# MCU.net
KiCad netlist of a schematic drawn in Altium Designer
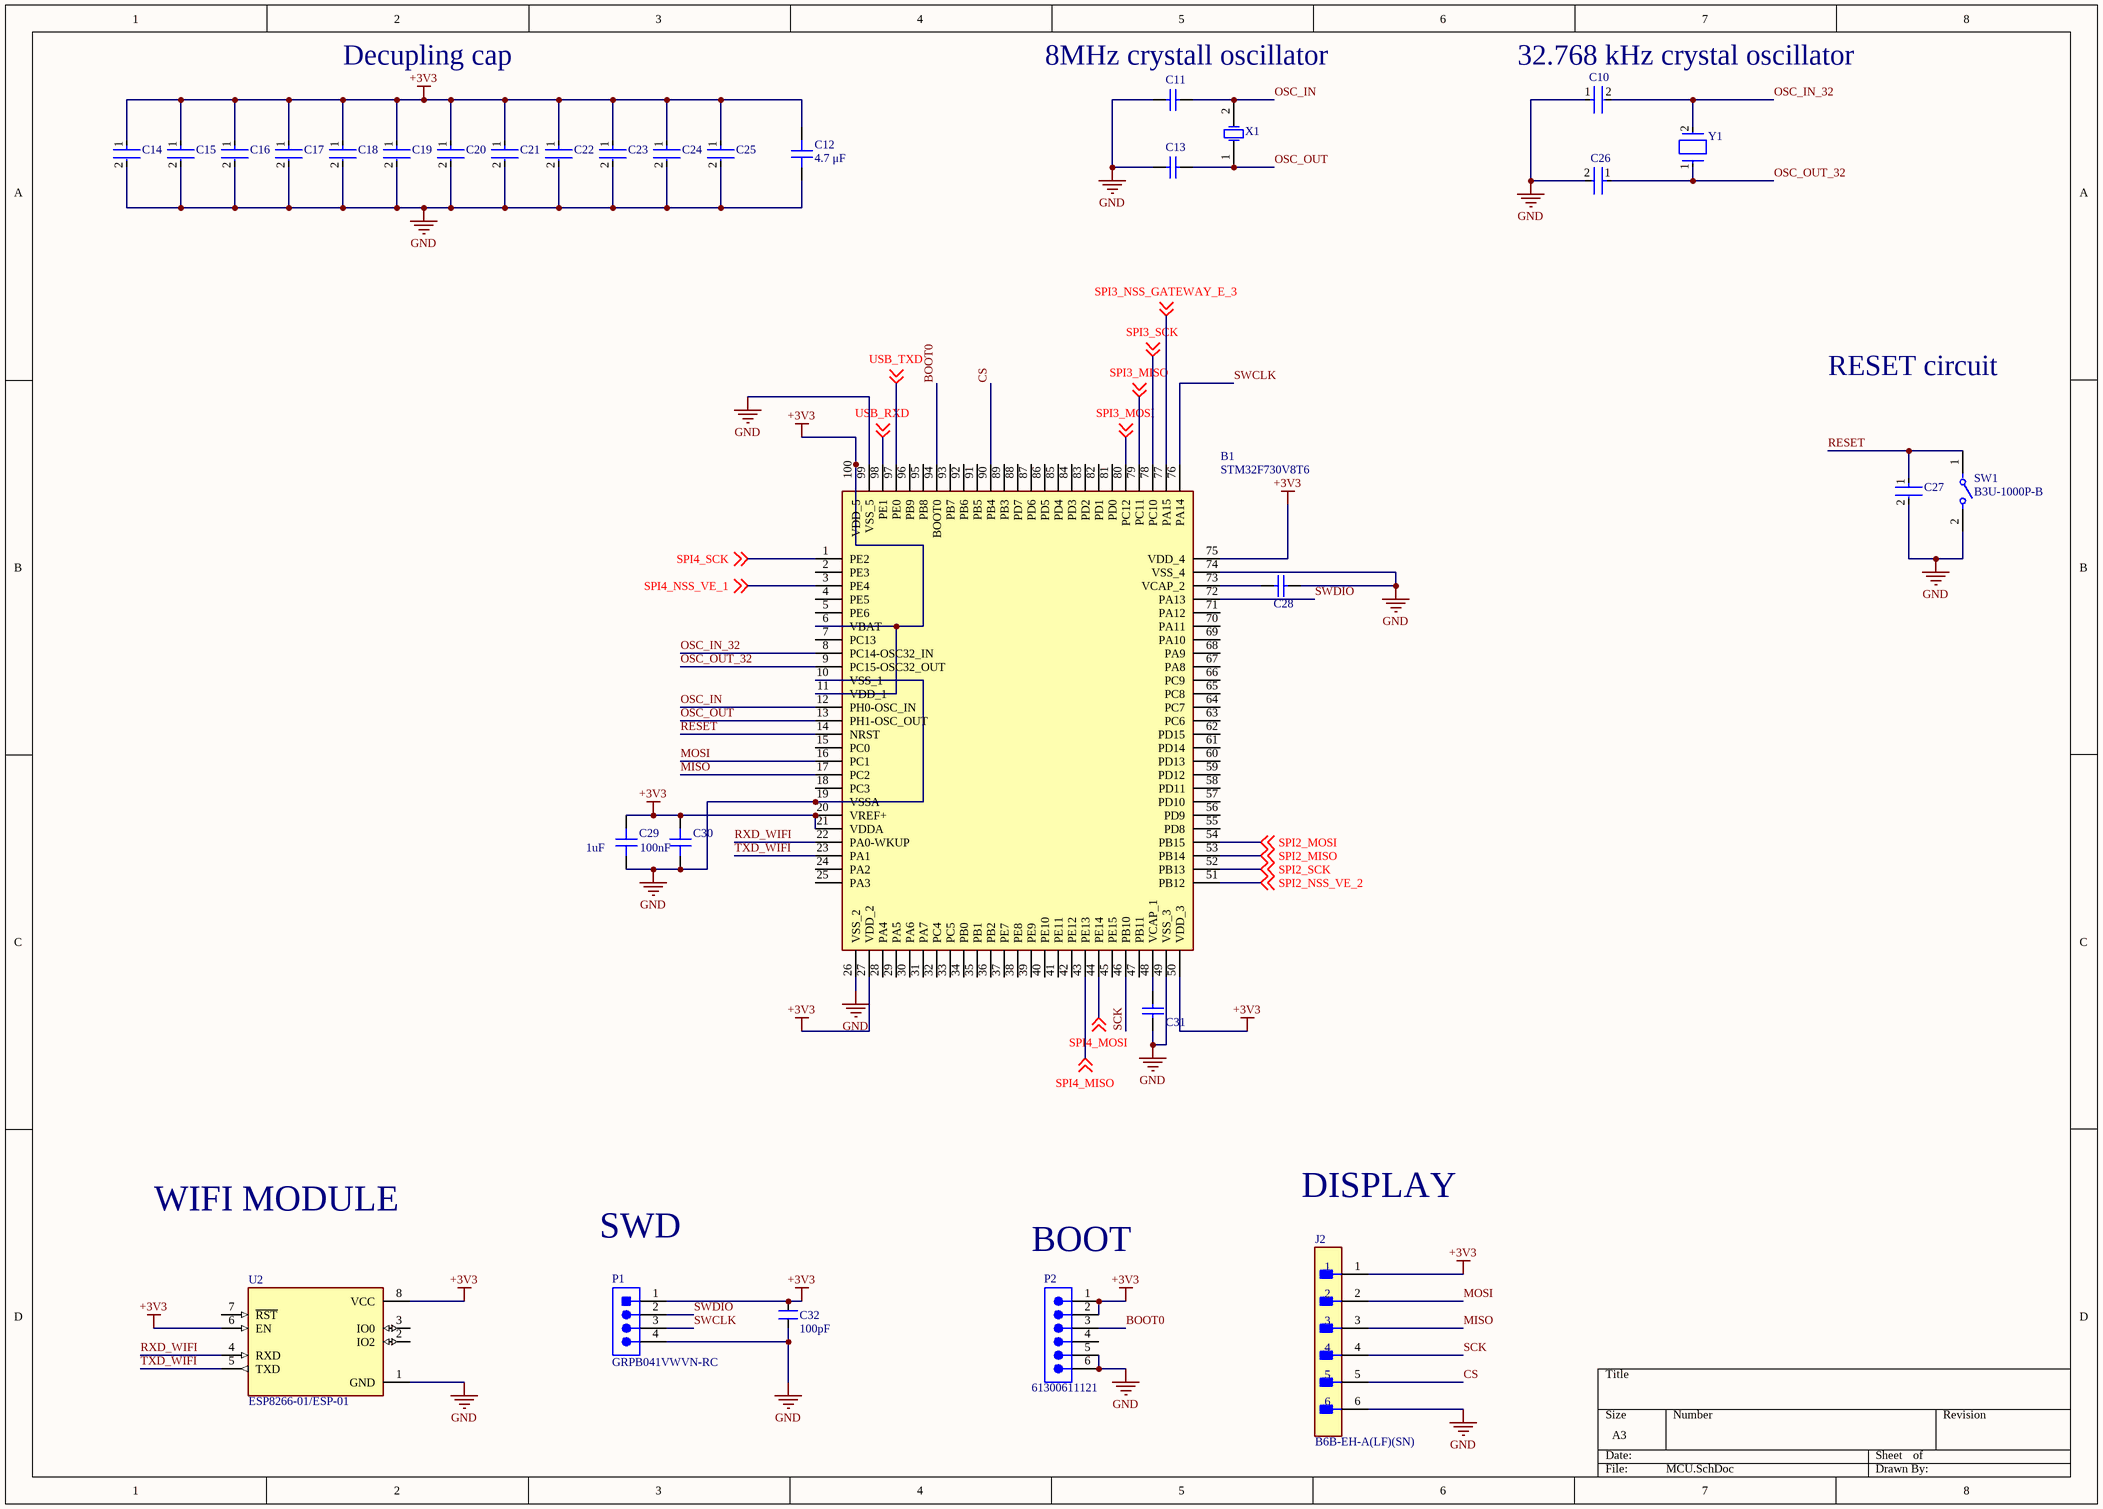
[diagram p0: MCU.SchDoc]

(export (version "E")
  (design (tool "Eeschema 10.0.6"))
  (components
    (comp (ref "B1")
      (value "STM32F730V8T6")
      (footprint "QFP50P1600X1600X160-100N")
      (description "STMICROELECTRONICS - STM32F730V8T6 - MCU, 32BIT, 216MHZ, LQFP-100")
      (fields (field (name "MOUSER PART NUMBER") "511-STM32F730V8T6"))
      (libsource (lib "STM32F730V8T6") (part "STM32F730V8T6"))
    )
    (comp (ref "C10")
      (value "C1005C0G1H070D050BA")
      (footprint "FP-C1005-050-0_05-IPC_A")
      (description "Multilayer Ceramic Capacitors 7pF ±0.5pF 50V C0G SMD 0402")
      (libsource (lib "Altium Content Vault") (part "b4654b650e69147ec39a6b967a45e02"))
    )
    (comp (ref "C11")
      (value "CC0603JRNPO9BN180")
      (footprint "CAPC1608X90X40LL10T20")
      (description "Chip Capacitor, 18 pF, +/- 5%, 50 V, -55 to 125 degC, 0603 (1608 Metric), RoHS, Tape and Reel")
      (fields (field (name "TOLERANCE") "1%"))
      (libsource (lib "Altium Content Vault") (part "CAP-NP-2"))
    )
    (comp (ref "C12")
      (value "4.7 μF")
      (footprint "CAP 0402_1005")
      (description "SMT Capacitor")
      (libsource (lib "Capacitor") (part "Cap 0402"))
    )
    (comp (ref "C13")
      (value "CC0603JRNPO9BN180")
      (footprint "CAPC1608X90X40LL10T20")
      (description "Chip Capacitor, 18 pF, +/- 5%, 50 V, -55 to 125 degC, 0603 (1608 Metric), RoHS, Tape and Reel")
      (fields (field (name "TOLERANCE") "1%"))
      (libsource (lib "Altium Content Vault") (part "CAP-NP-2"))
    )
    (comp (ref "C14")
      (value "GRM155R71H104KE14D")
      (footprint "FP-GRM155-0_05-IPC_B")
      (description "Chip Multilayer Ceramic Capacitors for General Purpose, 0402, 0.10uF, X7R, 15%, 10%, 50V")
      (fields (field (name "VOLTAGE") "50V") (field (name "TOLERANCE") "10%"))
      (libsource (lib "Altium Content Vault") (part "02cd4be3c70576c341d710602a673aa"))
    )
    (comp (ref "C15")
      (value "GRM155R71H104KE14D")
      (footprint "FP-GRM155-0_05-IPC_B")
      (description "Chip Multilayer Ceramic Capacitors for General Purpose, 0402, 0.10uF, X7R, 15%, 10%, 50V")
      (fields (field (name "VOLTAGE") "50V") (field (name "TOLERANCE") "10%"))
      (libsource (lib "Altium Content Vault") (part "02cd4be3c70576c341d710602a673aa"))
    )
    (comp (ref "C16")
      (value "GRM155R71H104KE14D")
      (footprint "FP-GRM155-0_05-IPC_B")
      (description "Chip Multilayer Ceramic Capacitors for General Purpose, 0402, 0.10uF, X7R, 15%, 10%, 50V")
      (fields (field (name "VOLTAGE") "50V") (field (name "TOLERANCE") "10%"))
      (libsource (lib "Altium Content Vault") (part "02cd4be3c70576c341d710602a673aa"))
    )
    (comp (ref "C17")
      (value "GRM155R71H104KE14D")
      (footprint "FP-GRM155-0_05-IPC_B")
      (description "Chip Multilayer Ceramic Capacitors for General Purpose, 0402, 0.10uF, X7R, 15%, 10%, 50V")
      (fields (field (name "VOLTAGE") "50V") (field (name "TOLERANCE") "10%"))
      (libsource (lib "Altium Content Vault") (part "02cd4be3c70576c341d710602a673aa"))
    )
    (comp (ref "C18")
      (value "GRM155R71H104KE14D")
      (footprint "FP-GRM155-0_05-IPC_B")
      (description "Chip Multilayer Ceramic Capacitors for General Purpose, 0402, 0.10uF, X7R, 15%, 10%, 50V")
      (fields (field (name "VOLTAGE") "50V") (field (name "TOLERANCE") "10%"))
      (libsource (lib "Altium Content Vault") (part "02cd4be3c70576c341d710602a673aa"))
    )
    (comp (ref "C19")
      (value "GRM155R71H104KE14D")
      (footprint "FP-GRM155-0_05-IPC_B")
      (description "Chip Multilayer Ceramic Capacitors for General Purpose, 0402, 0.10uF, X7R, 15%, 10%, 50V")
      (fields (field (name "VOLTAGE") "50V") (field (name "TOLERANCE") "10%"))
      (libsource (lib "Altium Content Vault") (part "02cd4be3c70576c341d710602a673aa"))
    )
    (comp (ref "C20")
      (value "GRM155R71H104KE14D")
      (footprint "FP-GRM155-0_05-IPC_B")
      (description "Chip Multilayer Ceramic Capacitors for General Purpose, 0402, 0.10uF, X7R, 15%, 10%, 50V")
      (fields (field (name "VOLTAGE") "50V") (field (name "TOLERANCE") "10%"))
      (libsource (lib "Altium Content Vault") (part "02cd4be3c70576c341d710602a673aa"))
    )
    (comp (ref "C21")
      (value "GRM155R71H104KE14D")
      (footprint "FP-GRM155-0_05-IPC_B")
      (description "Chip Multilayer Ceramic Capacitors for General Purpose, 0402, 0.10uF, X7R, 15%, 10%, 50V")
      (fields (field (name "VOLTAGE") "50V") (field (name "TOLERANCE") "10%"))
      (libsource (lib "Altium Content Vault") (part "02cd4be3c70576c341d710602a673aa"))
    )
    (comp (ref "C22")
      (value "GRM155R71H104KE14D")
      (footprint "FP-GRM155-0_05-IPC_B")
      (description "Chip Multilayer Ceramic Capacitors for General Purpose, 0402, 0.10uF, X7R, 15%, 10%, 50V")
      (fields (field (name "VOLTAGE") "50V") (field (name "TOLERANCE") "10%"))
      (libsource (lib "Altium Content Vault") (part "02cd4be3c70576c341d710602a673aa"))
    )
    (comp (ref "C23")
      (value "GRM155R71H104KE14D")
      (footprint "FP-GRM155-0_05-IPC_B")
      (description "Chip Multilayer Ceramic Capacitors for General Purpose, 0402, 0.10uF, X7R, 15%, 10%, 50V")
      (fields (field (name "VOLTAGE") "50V") (field (name "TOLERANCE") "10%"))
      (libsource (lib "Altium Content Vault") (part "02cd4be3c70576c341d710602a673aa"))
    )
    (comp (ref "C24")
      (value "GRM155R71H104KE14D")
      (footprint "FP-GRM155-0_05-IPC_B")
      (description "Chip Multilayer Ceramic Capacitors for General Purpose, 0402, 0.10uF, X7R, 15%, 10%, 50V")
      (fields (field (name "VOLTAGE") "50V") (field (name "TOLERANCE") "10%"))
      (libsource (lib "Altium Content Vault") (part "02cd4be3c70576c341d710602a673aa"))
    )
    (comp (ref "C25")
      (value "GRM155R71H104KE14D")
      (footprint "FP-GRM155-0_05-IPC_B")
      (description "Chip Multilayer Ceramic Capacitors for General Purpose, 0402, 0.10uF, X7R, 15%, 10%, 50V")
      (fields (field (name "VOLTAGE") "50V") (field (name "TOLERANCE") "10%"))
      (libsource (lib "Altium Content Vault") (part "02cd4be3c70576c341d710602a673aa"))
    )
    (comp (ref "C26")
      (value "C1005C0G1H070D050BA")
      (footprint "FP-C1005-050-0_05-IPC_A")
      (description "Multilayer Ceramic Capacitors 7pF ±0.5pF 50V C0G SMD 0402")
      (libsource (lib "Altium Content Vault") (part "b4654b650e69147ec39a6b967a45e02"))
    )
    (comp (ref "C27")
      (value "GRM155R71H104KE14D")
      (footprint "FP-GRM155-0_05-IPC_B")
      (description "Chip Multilayer Ceramic Capacitors for General Purpose, 0402, 0.10uF, X7R, 15%, 10%, 50V")
      (fields (field (name "VOLTAGE") "50V") (field (name "TOLERANCE") "10%"))
      (libsource (lib "Altium Content Vault") (part "02cd4be3c70576c341d710602a673aa"))
    )
    (comp (ref "C28")
      (value "C0603C225K9PACTU")
      (footprint "CAPC1608X90X35LL15T15")
      (fields (field (name "MANUFACTURER") "Kemet"))
      (libsource (lib "Altium Content Vault") (part "CAP"))
    )
    (comp (ref "C29")
      (value "1uF")
      (footprint "CAP 0402_1005")
      (description "SMT Capacitor")
      (libsource (lib "Capacitor") (part "Cap 0402"))
    )
    (comp (ref "C30")
      (value "100nF")
      (footprint "CAP 0402_1005")
      (description "SMT Capacitor")
      (libsource (lib "Capacitor") (part "Cap 0402"))
    )
    (comp (ref "C31")
      (value "C0603C225K9PACTU")
      (footprint "CAPC1608X90X35LL15T15")
      (fields (field (name "MANUFACTURER") "Kemet"))
      (libsource (lib "Altium Content Vault") (part "CAP"))
    )
    (comp (ref "C32")
      (value "100pF")
      (footprint "CAP_0805")
      (description "100pF ±5% 100V Ceramic Capacitor C0G, NP0 0805 (2012 Metric)")
      (fields
        (field (name "MANUFACTURER") "Murata")
        (field (name "MANUFACTURER PART NUMBER") "CL21C101JC61PNC")
      )
      (libsource (lib "ESTEEMPCBLIB") (part "CAP_100pF-100V-5%-0805"))
    )
    (comp (ref "J2")
      (value "B6B-EH-A(LF)(SN)")
      (footprint "FP-B6B-EH-A_LF_SN-MFG")
      (description "CONN HEADER VERT 6POS 2.5MM")
      (libsource (lib "Altium Content Vault") (part "f2cb566baf1c37ab5a3b8e90bbeafd6"))
    )
    (comp (ref "P1")
      (value "GRPB041VWVN-RC")
      (footprint "SLIN-GRPB041VWVN-RC_V")
      (fields (field (name "MANUFACTURER") "Sullins"))
      (libsource (lib "Altium Content Vault") (part "CN-1P-M-R4"))
    )
    (comp (ref "P2")
      (value "61300611121")
      (footprint "61300611121")
      (libsource (lib "Altium Content Vault") (part "Header_Male_1R_06P"))
    )
    (comp (ref "SW1")
      (value "B3U-1000P-B")
      (footprint "FP-B3U-1000P-B-MFG")
      (description "SWITCH TACTILE SPST-NO 0.05A 12V")
      (fields
        (field (name "OCTOPART") "https://octopart.com/b3u-1000p-b-omron-1057356")
        (field (name "MANUFACTURER") "Omron")
      )
      (libsource (lib "Altium Content Vault") (part "bb27bde45df87f1f469753f287ef5ae"))
    )
    (comp (ref "U2")
      (value "ESP8266-01/ESP-01")
      (footprint "XCVR_ESP8266-01/ESP-01")
      (libsource (lib "ESP8266 wifi module") (part "ESP8266-01/ESP-01"))
    )
    (comp (ref "X1")
      (value "ECS-80-18-5PX-TR")
      (footprint "ECS-80-18-5PX-TR_V")
      (description "Low Profile Quartz Crystal, 8.0 MHz, 2-Pin SMD, RoHS, Tape and Reel")
      (fields (field (name "TOLERANCE") "30PPM") (field (name "MANUFACTURER") "ECS"))
      (libsource (lib "Altium Content Vault") (part "XTAL_1-2-2"))
    )
    (comp (ref "Y1")
      (value "ABS07-32.768KHZ-7-T")
      (footprint "FP-ABS07-MFG")
      (description "Crystal 32.768kHz ±20ppm (Tol) 7pF FUND 70kΩ 2-Pin CSMD T/R")
      (fields (field (name "TOLERANCE") "20ppm"))
      (libsource (lib "Altium Content Vault") (part "c23a69dc6c9e2f18f2079038eb95dd1"))
    )
  )
  (nets
    (net (code "1") (name "+3V3") (class "Default")
      (node (ref "B1") (pin "100") (pinfunction "VDD_5_100") (pintype "passive"))
      (node (ref "B1") (pin "11") (pinfunction "VDD_1_11") (pintype "passive"))
      (node (ref "B1") (pin "20") (pinfunction "VREF+_20") (pintype "passive"))
      (node (ref "B1") (pin "21") (pinfunction "VDDA_21") (pintype "passive"))
      (node (ref "B1") (pin "27") (pinfunction "VDD_2_27") (pintype "passive"))
      (node (ref "B1") (pin "50") (pinfunction "VDD_3_50") (pintype "passive"))
      (node (ref "B1") (pin "6") (pinfunction "VBAT_6") (pintype "passive"))
      (node (ref "B1") (pin "75") (pinfunction "VDD_4_75") (pintype "passive"))
      (node (ref "C12") (pin "2") (pinfunction "2_2") (pintype "passive"))
      (node (ref "C14") (pin "1") (pinfunction "1_1") (pintype "passive"))
      (node (ref "C15") (pin "1") (pinfunction "1_1") (pintype "passive"))
      (node (ref "C16") (pin "1") (pinfunction "1_1") (pintype "passive"))
      (node (ref "C17") (pin "1") (pinfunction "1_1") (pintype "passive"))
      (node (ref "C18") (pin "1") (pinfunction "1_1") (pintype "passive"))
      (node (ref "C19") (pin "1") (pinfunction "1_1") (pintype "passive"))
      (node (ref "C20") (pin "1") (pinfunction "1_1") (pintype "passive"))
      (node (ref "C21") (pin "1") (pinfunction "1_1") (pintype "passive"))
      (node (ref "C22") (pin "1") (pinfunction "1_1") (pintype "passive"))
      (node (ref "C23") (pin "1") (pinfunction "1_1") (pintype "passive"))
      (node (ref "C24") (pin "1") (pinfunction "1_1") (pintype "passive"))
      (node (ref "C25") (pin "1") (pinfunction "1_1") (pintype "passive"))
      (node (ref "C29") (pin "2") (pinfunction "2_2") (pintype "passive"))
      (node (ref "C30") (pin "2") (pinfunction "2_2") (pintype "passive"))
      (node (ref "C32") (pin "2") (pinfunction "2_2") (pintype "passive"))
      (node (ref "J2") (pin "1") (pinfunction "1_1") (pintype "passive"))
      (node (ref "P1") (pin "1") (pinfunction "1_1") (pintype "passive"))
      (node (ref "P2") (pin "1") (pinfunction "1_1") (pintype "passive"))
      (node (ref "P2") (pin "2") (pinfunction "2_2") (pintype "passive"))
      (node (ref "U2") (pin "6") (pinfunction "EN_6") (pintype "input"))
      (node (ref "U2") (pin "8") (pinfunction "VCC_8") (pintype "power_in"))
    )
    (net (code "2") (name "/BOOT0") (class "Default")
      (node (ref "B1") (pin "94") (pinfunction "BOOT0_94") (pintype "passive"))
      (node (ref "P2") (pin "3") (pinfunction "3_3") (pintype "passive"))
    )
    (net (code "3") (name "/CS") (class "Default")
      (node (ref "B1") (pin "90") (pinfunction "PB4_90") (pintype "passive"))
      (node (ref "J2") (pin "5") (pinfunction "5_5") (pintype "passive"))
    )
    (net (code "4") (name "/MISO") (class "Default")
      (node (ref "B1") (pin "17") (pinfunction "PC2_17") (pintype "passive"))
      (node (ref "J2") (pin "3") (pinfunction "3_3") (pintype "passive"))
    )
    (net (code "5") (name "/MOSI") (class "Default")
      (node (ref "B1") (pin "16") (pinfunction "PC1_16") (pintype "passive"))
      (node (ref "J2") (pin "2") (pinfunction "2_2") (pintype "passive"))
    )
    (net (code "6") (name "/OSC_IN") (class "Default")
      (node (ref "B1") (pin "12") (pinfunction "PH0-OSC_IN_12") (pintype "passive"))
      (node (ref "C11") (pin "1") (pinfunction "1_1") (pintype "passive"))
      (node (ref "X1") (pin "2") (pinfunction "X2_2") (pintype "passive"))
    )
    (net (code "7") (name "/OSC_IN_32") (class "Default")
      (node (ref "B1") (pin "8") (pinfunction "PC14-OSC32_IN_8") (pintype "passive"))
      (node (ref "C10") (pin "2") (pinfunction "2_2") (pintype "passive"))
      (node (ref "Y1") (pin "2") (pinfunction "2_2") (pintype "passive"))
    )
    (net (code "8") (name "/OSC_OUT") (class "Default")
      (node (ref "B1") (pin "13") (pinfunction "PH1-OSC_OUT_13") (pintype "passive"))
      (node (ref "C13") (pin "1") (pinfunction "1_1") (pintype "passive"))
      (node (ref "X1") (pin "1") (pinfunction "X1_1") (pintype "passive"))
    )
    (net (code "9") (name "/OSC_OUT_32") (class "Default")
      (node (ref "B1") (pin "9") (pinfunction "PC15-OSC32_OUT_9") (pintype "passive"))
      (node (ref "C26") (pin "1") (pinfunction "1_1") (pintype "passive"))
      (node (ref "Y1") (pin "1") (pinfunction "1_1") (pintype "passive"))
    )
    (net (code "10") (name "/RESET") (class "Default")
      (node (ref "B1") (pin "14") (pinfunction "NRST_14") (pintype "passive"))
      (node (ref "C27") (pin "1") (pinfunction "1_1") (pintype "passive"))
      (node (ref "SW1") (pin "1") (pinfunction "1_1") (pintype "passive"))
    )
    (net (code "11") (name "/RXD_WIFI") (class "Default")
      (node (ref "B1") (pin "22") (pinfunction "PA0-WKUP_22") (pintype "passive"))
      (node (ref "U2") (pin "4") (pinfunction "RXD_4") (pintype "input"))
    )
    (net (code "12") (name "/SCK") (class "Default")
      (node (ref "B1") (pin "46") (pinfunction "PB10_46") (pintype "passive"))
      (node (ref "J2") (pin "4") (pinfunction "4_4") (pintype "passive"))
    )
    (net (code "13") (name "/SWCLK") (class "Default")
      (node (ref "B1") (pin "76") (pinfunction "PA14_76") (pintype "passive"))
      (node (ref "P1") (pin "3") (pinfunction "3_3") (pintype "passive"))
    )
    (net (code "14") (name "/SWDIO") (class "Default")
      (node (ref "B1") (pin "72") (pinfunction "PA13_72") (pintype "passive"))
      (node (ref "P1") (pin "2") (pinfunction "2_2") (pintype "passive"))
    )
    (net (code "15") (name "/TXD_WIFI") (class "Default")
      (node (ref "B1") (pin "23") (pinfunction "PA1_23") (pintype "passive"))
      (node (ref "U2") (pin "5") (pinfunction "TXD_5") (pintype "output"))
    )
    (net (code "16") (name "GND") (class "Default")
      (node (ref "B1") (pin "10") (pinfunction "VSS_1_10") (pintype "passive"))
      (node (ref "B1") (pin "19") (pinfunction "VSSA_19") (pintype "passive"))
      (node (ref "B1") (pin "26") (pinfunction "VSS_2_26") (pintype "passive"))
      (node (ref "B1") (pin "49") (pinfunction "VSS_3_49") (pintype "passive"))
      (node (ref "B1") (pin "74") (pinfunction "VSS_4_74") (pintype "passive"))
      (node (ref "B1") (pin "99") (pinfunction "VSS_5_99") (pintype "passive"))
      (node (ref "C10") (pin "1") (pinfunction "1_1") (pintype "passive"))
      (node (ref "C11") (pin "2") (pinfunction "2_2") (pintype "passive"))
      (node (ref "C12") (pin "1") (pinfunction "1_1") (pintype "passive"))
      (node (ref "C13") (pin "2") (pinfunction "2_2") (pintype "passive"))
      (node (ref "C14") (pin "2") (pinfunction "2_2") (pintype "passive"))
      (node (ref "C15") (pin "2") (pinfunction "2_2") (pintype "passive"))
      (node (ref "C16") (pin "2") (pinfunction "2_2") (pintype "passive"))
      (node (ref "C17") (pin "2") (pinfunction "2_2") (pintype "passive"))
      (node (ref "C18") (pin "2") (pinfunction "2_2") (pintype "passive"))
      (node (ref "C19") (pin "2") (pinfunction "2_2") (pintype "passive"))
      (node (ref "C20") (pin "2") (pinfunction "2_2") (pintype "passive"))
      (node (ref "C21") (pin "2") (pinfunction "2_2") (pintype "passive"))
      (node (ref "C22") (pin "2") (pinfunction "2_2") (pintype "passive"))
      (node (ref "C23") (pin "2") (pinfunction "2_2") (pintype "passive"))
      (node (ref "C24") (pin "2") (pinfunction "2_2") (pintype "passive"))
      (node (ref "C25") (pin "2") (pinfunction "2_2") (pintype "passive"))
      (node (ref "C26") (pin "2") (pinfunction "2_2") (pintype "passive"))
      (node (ref "C27") (pin "2") (pinfunction "2_2") (pintype "passive"))
      (node (ref "C28") (pin "1") (pinfunction "1_1") (pintype "passive"))
      (node (ref "C29") (pin "1") (pinfunction "1_1") (pintype "passive"))
      (node (ref "C30") (pin "1") (pinfunction "1_1") (pintype "passive"))
      (node (ref "C31") (pin "1") (pinfunction "1_1") (pintype "passive"))
      (node (ref "C32") (pin "1") (pinfunction "1_1") (pintype "passive"))
      (node (ref "J2") (pin "6") (pinfunction "6_6") (pintype "passive"))
      (node (ref "P1") (pin "4") (pinfunction "4_4") (pintype "passive"))
      (node (ref "P2") (pin "5") (pinfunction "5_5") (pintype "passive"))
      (node (ref "P2") (pin "6") (pinfunction "6_6") (pintype "passive"))
      (node (ref "SW1") (pin "2") (pinfunction "2_2") (pintype "passive"))
      (node (ref "U2") (pin "1") (pinfunction "GND_1") (pintype "power_in"))
    )
    (net (code "17") (name "Net-(B1-VCAP_1)") (class "Default")
      (node (ref "B1") (pin "48") (pinfunction "VCAP_1_48") (pintype "passive"))
      (node (ref "C31") (pin "2") (pinfunction "2_2") (pintype "passive"))
    )
    (net (code "18") (name "Net-(B1-VCAP_2)") (class "Default")
      (node (ref "B1") (pin "73") (pinfunction "VCAP_2_73") (pintype "passive"))
      (node (ref "C28") (pin "2") (pinfunction "2_2") (pintype "passive"))
    )
    (net (code "19") (name "SPI2_MISO") (class "Default")
      (node (ref "B1") (pin "53") (pinfunction "PB14_53") (pintype "passive"))
    )
    (net (code "20") (name "SPI2_MOSI") (class "Default")
      (node (ref "B1") (pin "54") (pinfunction "PB15_54") (pintype "passive"))
    )
    (net (code "21") (name "SPI2_NSS_VE_2") (class "Default")
      (node (ref "B1") (pin "51") (pinfunction "PB12_51") (pintype "passive"))
    )
    (net (code "22") (name "SPI2_SCK") (class "Default")
      (node (ref "B1") (pin "52") (pinfunction "PB13_52") (pintype "passive"))
    )
    (net (code "23") (name "SPI3_MISO") (class "Default")
      (node (ref "B1") (pin "79") (pinfunction "PC11_79") (pintype "passive"))
    )
    (net (code "24") (name "SPI3_MOSI") (class "Default")
      (node (ref "B1") (pin "80") (pinfunction "PC12_80") (pintype "passive"))
    )
    (net (code "25") (name "SPI3_NSS_GATEWAY_E_3") (class "Default")
      (node (ref "B1") (pin "77") (pinfunction "PA15_77") (pintype "passive"))
    )
    (net (code "26") (name "SPI3_SCK") (class "Default")
      (node (ref "B1") (pin "78") (pinfunction "PC10_78") (pintype "passive"))
    )
    (net (code "27") (name "SPI4_MISO") (class "Default")
      (node (ref "B1") (pin "43") (pinfunction "PE13_43") (pintype "passive"))
    )
    (net (code "28") (name "SPI4_MOSI") (class "Default")
      (node (ref "B1") (pin "44") (pinfunction "PE14_44") (pintype "passive"))
    )
    (net (code "29") (name "SPI4_NSS_VE_1") (class "Default")
      (node (ref "B1") (pin "3") (pinfunction "PE4_3") (pintype "passive"))
    )
    (net (code "30") (name "SPI4_SCK") (class "Default")
      (node (ref "B1") (pin "1") (pinfunction "PE2_1") (pintype "passive"))
    )
    (net (code "31") (name "USB_RXD") (class "Default")
      (node (ref "B1") (pin "98") (pinfunction "PE1_98") (pintype "passive"))
    )
    (net (code "32") (name "USB_TXD") (class "Default")
      (node (ref "B1") (pin "97") (pinfunction "PE0_97") (pintype "passive"))
    )
    (net (code "33") (name "unconnected-(B1-PA2-Pad24)") (class "Default")
      (node (ref "B1") (pin "24") (pinfunction "PA2_24") (pintype "passive"))
    )
    (net (code "34") (name "unconnected-(B1-PA3-Pad25)") (class "Default")
      (node (ref "B1") (pin "25") (pinfunction "PA3_25") (pintype "passive"))
    )
    (net (code "35") (name "unconnected-(B1-PA4-Pad28)") (class "Default")
      (node (ref "B1") (pin "28") (pinfunction "PA4_28") (pintype "passive"))
    )
    (net (code "36") (name "unconnected-(B1-PA5-Pad29)") (class "Default")
      (node (ref "B1") (pin "29") (pinfunction "PA5_29") (pintype "passive"))
    )
    (net (code "37") (name "unconnected-(B1-PA6-Pad30)") (class "Default")
      (node (ref "B1") (pin "30") (pinfunction "PA6_30") (pintype "passive"))
    )
    (net (code "38") (name "unconnected-(B1-PA7-Pad31)") (class "Default")
      (node (ref "B1") (pin "31") (pinfunction "PA7_31") (pintype "passive"))
    )
    (net (code "39") (name "unconnected-(B1-PA8-Pad67)") (class "Default")
      (node (ref "B1") (pin "67") (pinfunction "PA8_67") (pintype "passive"))
    )
    (net (code "40") (name "unconnected-(B1-PA9-Pad68)") (class "Default")
      (node (ref "B1") (pin "68") (pinfunction "PA9_68") (pintype "passive"))
    )
    (net (code "41") (name "unconnected-(B1-PA10-Pad69)") (class "Default")
      (node (ref "B1") (pin "69") (pinfunction "PA10_69") (pintype "passive"))
    )
    (net (code "42") (name "unconnected-(B1-PA11-Pad70)") (class "Default")
      (node (ref "B1") (pin "70") (pinfunction "PA11_70") (pintype "passive"))
    )
    (net (code "43") (name "unconnected-(B1-PA12-Pad71)") (class "Default")
      (node (ref "B1") (pin "71") (pinfunction "PA12_71") (pintype "passive"))
    )
    (net (code "44") (name "unconnected-(B1-PB0-Pad34)") (class "Default")
      (node (ref "B1") (pin "34") (pinfunction "PB0_34") (pintype "passive"))
    )
    (net (code "45") (name "unconnected-(B1-PB1-Pad35)") (class "Default")
      (node (ref "B1") (pin "35") (pinfunction "PB1_35") (pintype "passive"))
    )
    (net (code "46") (name "unconnected-(B1-PB2-Pad36)") (class "Default")
      (node (ref "B1") (pin "36") (pinfunction "PB2_36") (pintype "passive"))
    )
    (net (code "47") (name "unconnected-(B1-PB3-Pad89)") (class "Default")
      (node (ref "B1") (pin "89") (pinfunction "PB3_89") (pintype "passive"))
    )
    (net (code "48") (name "unconnected-(B1-PB5-Pad91)") (class "Default")
      (node (ref "B1") (pin "91") (pinfunction "PB5_91") (pintype "passive"))
    )
    (net (code "49") (name "unconnected-(B1-PB6-Pad92)") (class "Default")
      (node (ref "B1") (pin "92") (pinfunction "PB6_92") (pintype "passive"))
    )
    (net (code "50") (name "unconnected-(B1-PB7-Pad93)") (class "Default")
      (node (ref "B1") (pin "93") (pinfunction "PB7_93") (pintype "passive"))
    )
    (net (code "51") (name "unconnected-(B1-PB8-Pad95)") (class "Default")
      (node (ref "B1") (pin "95") (pinfunction "PB8_95") (pintype "passive"))
    )
    (net (code "52") (name "unconnected-(B1-PB9-Pad96)") (class "Default")
      (node (ref "B1") (pin "96") (pinfunction "PB9_96") (pintype "passive"))
    )
    (net (code "53") (name "unconnected-(B1-PB11-Pad47)") (class "Default")
      (node (ref "B1") (pin "47") (pinfunction "PB11_47") (pintype "passive"))
    )
    (net (code "54") (name "unconnected-(B1-PC0-Pad15)") (class "Default")
      (node (ref "B1") (pin "15") (pinfunction "PC0_15") (pintype "passive"))
    )
    (net (code "55") (name "unconnected-(B1-PC3-Pad18)") (class "Default")
      (node (ref "B1") (pin "18") (pinfunction "PC3_18") (pintype "passive"))
    )
    (net (code "56") (name "unconnected-(B1-PC4-Pad32)") (class "Default")
      (node (ref "B1") (pin "32") (pinfunction "PC4_32") (pintype "passive"))
    )
    (net (code "57") (name "unconnected-(B1-PC5-Pad33)") (class "Default")
      (node (ref "B1") (pin "33") (pinfunction "PC5_33") (pintype "passive"))
    )
    (net (code "58") (name "unconnected-(B1-PC6-Pad63)") (class "Default")
      (node (ref "B1") (pin "63") (pinfunction "PC6_63") (pintype "passive"))
    )
    (net (code "59") (name "unconnected-(B1-PC7-Pad64)") (class "Default")
      (node (ref "B1") (pin "64") (pinfunction "PC7_64") (pintype "passive"))
    )
    (net (code "60") (name "unconnected-(B1-PC8-Pad65)") (class "Default")
      (node (ref "B1") (pin "65") (pinfunction "PC8_65") (pintype "passive"))
    )
    (net (code "61") (name "unconnected-(B1-PC9-Pad66)") (class "Default")
      (node (ref "B1") (pin "66") (pinfunction "PC9_66") (pintype "passive"))
    )
    (net (code "62") (name "unconnected-(B1-PC13-Pad7)") (class "Default")
      (node (ref "B1") (pin "7") (pinfunction "PC13_7") (pintype "passive"))
    )
    (net (code "63") (name "unconnected-(B1-PD0-Pad81)") (class "Default")
      (node (ref "B1") (pin "81") (pinfunction "PD0_81") (pintype "passive"))
    )
    (net (code "64") (name "unconnected-(B1-PD1-Pad82)") (class "Default")
      (node (ref "B1") (pin "82") (pinfunction "PD1_82") (pintype "passive"))
    )
    (net (code "65") (name "unconnected-(B1-PD2-Pad83)") (class "Default")
      (node (ref "B1") (pin "83") (pinfunction "PD2_83") (pintype "passive"))
    )
    (net (code "66") (name "unconnected-(B1-PD3-Pad84)") (class "Default")
      (node (ref "B1") (pin "84") (pinfunction "PD3_84") (pintype "passive"))
    )
    (net (code "67") (name "unconnected-(B1-PD4-Pad85)") (class "Default")
      (node (ref "B1") (pin "85") (pinfunction "PD4_85") (pintype "passive"))
    )
    (net (code "68") (name "unconnected-(B1-PD5-Pad86)") (class "Default")
      (node (ref "B1") (pin "86") (pinfunction "PD5_86") (pintype "passive"))
    )
    (net (code "69") (name "unconnected-(B1-PD6-Pad87)") (class "Default")
      (node (ref "B1") (pin "87") (pinfunction "PD6_87") (pintype "passive"))
    )
    (net (code "70") (name "unconnected-(B1-PD7-Pad88)") (class "Default")
      (node (ref "B1") (pin "88") (pinfunction "PD7_88") (pintype "passive"))
    )
    (net (code "71") (name "unconnected-(B1-PD8-Pad55)") (class "Default")
      (node (ref "B1") (pin "55") (pinfunction "PD8_55") (pintype "passive"))
    )
    (net (code "72") (name "unconnected-(B1-PD9-Pad56)") (class "Default")
      (node (ref "B1") (pin "56") (pinfunction "PD9_56") (pintype "passive"))
    )
    (net (code "73") (name "unconnected-(B1-PD10-Pad57)") (class "Default")
      (node (ref "B1") (pin "57") (pinfunction "PD10_57") (pintype "passive"))
    )
    (net (code "74") (name "unconnected-(B1-PD11-Pad58)") (class "Default")
      (node (ref "B1") (pin "58") (pinfunction "PD11_58") (pintype "passive"))
    )
    (net (code "75") (name "unconnected-(B1-PD12-Pad59)") (class "Default")
      (node (ref "B1") (pin "59") (pinfunction "PD12_59") (pintype "passive"))
    )
    (net (code "76") (name "unconnected-(B1-PD13-Pad60)") (class "Default")
      (node (ref "B1") (pin "60") (pinfunction "PD13_60") (pintype "passive"))
    )
    (net (code "77") (name "unconnected-(B1-PD14-Pad61)") (class "Default")
      (node (ref "B1") (pin "61") (pinfunction "PD14_61") (pintype "passive"))
    )
    (net (code "78") (name "unconnected-(B1-PD15-Pad62)") (class "Default")
      (node (ref "B1") (pin "62") (pinfunction "PD15_62") (pintype "passive"))
    )
    (net (code "79") (name "unconnected-(B1-PE3-Pad2)") (class "Default")
      (node (ref "B1") (pin "2") (pinfunction "PE3_2") (pintype "passive"))
    )
    (net (code "80") (name "unconnected-(B1-PE5-Pad4)") (class "Default")
      (node (ref "B1") (pin "4") (pinfunction "PE5_4") (pintype "passive"))
    )
    (net (code "81") (name "unconnected-(B1-PE6-Pad5)") (class "Default")
      (node (ref "B1") (pin "5") (pinfunction "PE6_5") (pintype "passive"))
    )
    (net (code "82") (name "unconnected-(B1-PE7-Pad37)") (class "Default")
      (node (ref "B1") (pin "37") (pinfunction "PE7_37") (pintype "passive"))
    )
    (net (code "83") (name "unconnected-(B1-PE8-Pad38)") (class "Default")
      (node (ref "B1") (pin "38") (pinfunction "PE8_38") (pintype "passive"))
    )
    (net (code "84") (name "unconnected-(B1-PE9-Pad39)") (class "Default")
      (node (ref "B1") (pin "39") (pinfunction "PE9_39") (pintype "passive"))
    )
    (net (code "85") (name "unconnected-(B1-PE10-Pad40)") (class "Default")
      (node (ref "B1") (pin "40") (pinfunction "PE10_40") (pintype "passive"))
    )
    (net (code "86") (name "unconnected-(B1-PE11-Pad41)") (class "Default")
      (node (ref "B1") (pin "41") (pinfunction "PE11_41") (pintype "passive"))
    )
    (net (code "87") (name "unconnected-(B1-PE12-Pad42)") (class "Default")
      (node (ref "B1") (pin "42") (pinfunction "PE12_42") (pintype "passive"))
    )
    (net (code "88") (name "unconnected-(B1-PE15-Pad45)") (class "Default")
      (node (ref "B1") (pin "45") (pinfunction "PE15_45") (pintype "passive"))
    )
    (net (code "89") (name "unconnected-(P2-Pad4)") (class "Default")
      (node (ref "P2") (pin "4") (pinfunction "4_4") (pintype "passive"))
    )
    (net (code "90") (name "unconnected-(U2-IO0-Pad3)") (class "Default")
      (node (ref "U2") (pin "3") (pinfunction "IO0_3") (pintype "bidirectional"))
    )
    (net (code "91") (name "unconnected-(U2-IO2-Pad2)") (class "Default")
      (node (ref "U2") (pin "2") (pinfunction "IO2_2") (pintype "bidirectional"))
    )
    (net (code "92") (name "unconnected-(U2-~{RST}-Pad7)") (class "Default")
      (node (ref "U2") (pin "7") (pinfunction "~{RST}_7") (pintype "input"))
    )
  )
)
